# Pico_pinout.net
KiCad netlist of a schematic drawn in Altium Designer
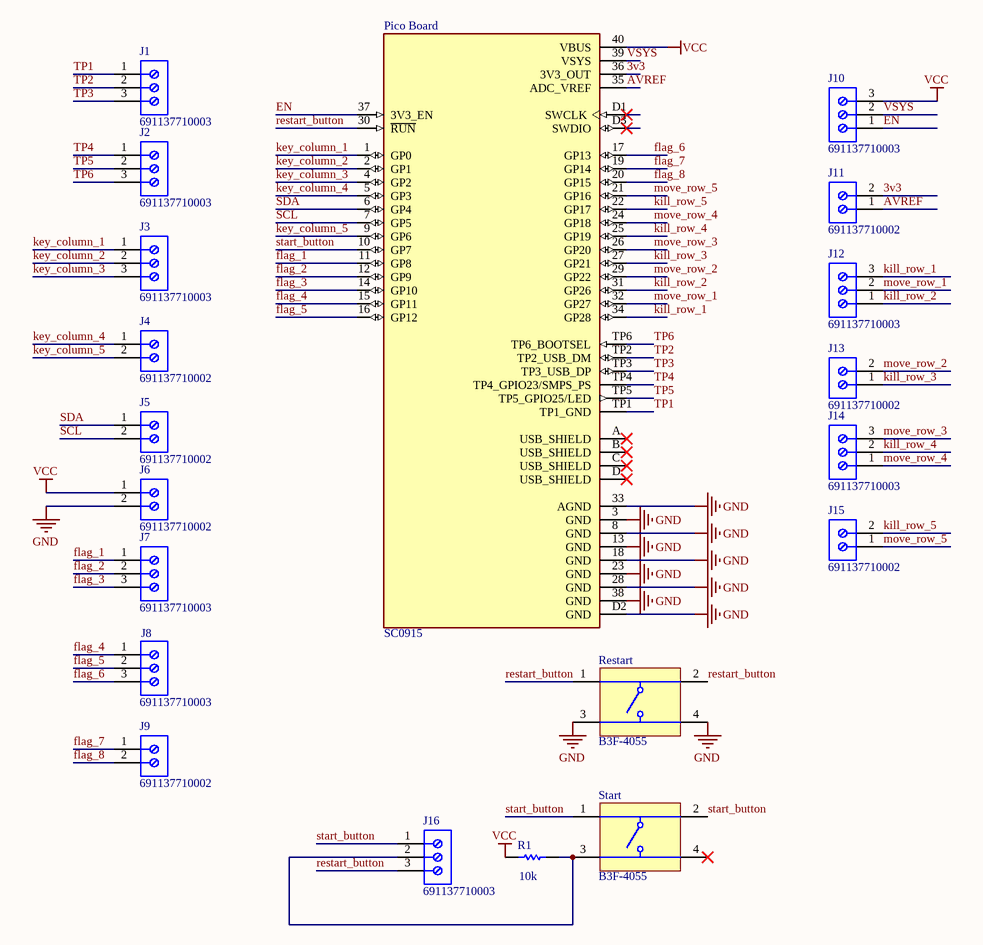
[diagram p0: Pico_pinout.SchDoc]

(export (version "E")
  (design (tool "Eeschema 10.0.6"))
  (components
    (comp (ref "J1")
      (value "691137710003")
      (footprint "691137710003")
      (libsource (lib "Altium Content Vault") (part "TBL - 1R - 03P - Screw"))
    )
    (comp (ref "J2")
      (value "691137710003")
      (footprint "691137710003")
      (libsource (lib "Altium Content Vault") (part "TBL - 1R - 03P - Screw"))
    )
    (comp (ref "J3")
      (value "691137710003")
      (footprint "691137710003")
      (libsource (lib "Altium Content Vault") (part "TBL - 1R - 03P - Screw"))
    )
    (comp (ref "J4")
      (value "691137710002")
      (footprint "691137710002")
      (libsource (lib "Altium Content Vault") (part "TBL - 1R - 02P - Screw"))
    )
    (comp (ref "J5")
      (value "691137710002")
      (footprint "691137710002")
      (libsource (lib "Altium Content Vault") (part "TBL - 1R - 02P - Screw"))
    )
    (comp (ref "J6")
      (value "691137710002")
      (footprint "691137710002")
      (libsource (lib "Altium Content Vault") (part "TBL - 1R - 02P - Screw"))
    )
    (comp (ref "J7")
      (value "691137710003")
      (footprint "691137710003")
      (libsource (lib "Altium Content Vault") (part "TBL - 1R - 03P - Screw"))
    )
    (comp (ref "J8")
      (value "691137710003")
      (footprint "691137710003")
      (libsource (lib "Altium Content Vault") (part "TBL - 1R - 03P - Screw"))
    )
    (comp (ref "J9")
      (value "691137710002")
      (footprint "691137710002")
      (libsource (lib "Altium Content Vault") (part "TBL - 1R - 02P - Screw"))
    )
    (comp (ref "J10")
      (value "691137710003")
      (footprint "691137710003")
      (libsource (lib "Altium Content Vault") (part "TBL - 1R - 03P - Screw"))
    )
    (comp (ref "J11")
      (value "691137710002")
      (footprint "691137710002")
      (libsource (lib "Altium Content Vault") (part "TBL - 1R - 02P - Screw"))
    )
    (comp (ref "J12")
      (value "691137710003")
      (footprint "691137710003")
      (libsource (lib "Altium Content Vault") (part "TBL - 1R - 03P - Screw"))
    )
    (comp (ref "J13")
      (value "691137710002")
      (footprint "691137710002")
      (libsource (lib "Altium Content Vault") (part "TBL - 1R - 02P - Screw"))
    )
    (comp (ref "J14")
      (value "691137710003")
      (footprint "691137710003")
      (libsource (lib "Altium Content Vault") (part "TBL - 1R - 03P - Screw"))
    )
    (comp (ref "J15")
      (value "691137710002")
      (footprint "691137710002")
      (libsource (lib "Altium Content Vault") (part "TBL - 1R - 02P - Screw"))
    )
    (comp (ref "J16")
      (value "691137710003")
      (footprint "691137710003")
      (libsource (lib "Altium Content Vault") (part "TBL - 1R - 03P - Screw"))
    )
    (comp (ref "Pico Board")
      (value "SC0915")
      (footprint "MODULE_SC0915")
      (description "RP2040 Raspberry Pi Pico series ARMÂ® CortexÂ®-M0+ MCU 32-Bit Embedded Evaluation Board")
      (fields (field (name "MF") "Raspberry Pi"))
      (libsource (lib "SC0915 (1)") (part "SC0915"))
    )
    (comp (ref "R1")
      (value "10k")
      (footprint "RESC3116X65X40ML10T20")
      (description "Chip Resistor, 10 KOhm, +/- 1%, 0.25 W, -55 to 155 degC, 1206 (3216 Metric), RoHS, Tape and Reel")
      (fields (field (name "TOLERANCE") "1%") (field (name "MANUFACTURER") "Yageo"))
      (libsource (lib "Altium Content Vault") (part "RES-2"))
    )
    (comp (ref "Restart")
      (value "B3F-4055")
      (footprint "OMRON-B3F-4055_V")
      (description "Tactile Switch, 1 to 50 mA, 100 mOhm Max, 5 to 24 VDC, -25 to 70 degC, 4-Pin THD, RoHS, Bulk")
      (fields (field (name "MANUFACTURER") "OmronElectronics"))
      (libsource (lib "Altium Content Vault") (part "SW-SPST-4_A"))
    )
    (comp (ref "Start")
      (value "B3F-4055")
      (footprint "OMRON-B3F-4055_V")
      (description "Tactile Switch, 1 to 50 mA, 100 mOhm Max, 5 to 24 VDC, -25 to 70 degC, 4-Pin THD, RoHS, Bulk")
      (fields (field (name "MANUFACTURER") "OmronElectronics"))
      (libsource (lib "Altium Content Vault") (part "SW-SPST-4_A"))
    )
  )
  (nets
    (net (code "1") (name "/3v3") (class "Default")
      (node (ref "J11") (pin "2") (pinfunction "2_2") (pintype "passive"))
      (node (ref "Pico Board") (pin "36") (pinfunction "3V3_OUT_36") (pintype "power_in"))
    )
    (net (code "2") (name "/AVREF") (class "Default")
      (node (ref "J11") (pin "1") (pinfunction "1_1") (pintype "passive"))
      (node (ref "Pico Board") (pin "35") (pinfunction "ADC_VREF_35") (pintype "power_in"))
    )
    (net (code "3") (name "/EN") (class "Default")
      (node (ref "J10") (pin "1") (pinfunction "1_1") (pintype "passive"))
      (node (ref "Pico Board") (pin "37") (pinfunction "3V3_EN_37") (pintype "input"))
    )
    (net (code "4") (name "/SCL") (class "Default")
      (node (ref "J5") (pin "2") (pinfunction "2_2") (pintype "passive"))
      (node (ref "Pico Board") (pin "7") (pinfunction "GP5_7") (pintype "bidirectional"))
    )
    (net (code "5") (name "/SDA") (class "Default")
      (node (ref "J5") (pin "1") (pinfunction "1_1") (pintype "passive"))
      (node (ref "Pico Board") (pin "6") (pinfunction "GP4_6") (pintype "bidirectional"))
    )
    (net (code "6") (name "/TP1") (class "Default")
      (node (ref "J1") (pin "1") (pinfunction "1_1") (pintype "passive"))
      (node (ref "Pico Board") (pin "TP1") (pinfunction "TP1_GND_TP1") (pintype "power_in"))
    )
    (net (code "7") (name "/TP2") (class "Default")
      (node (ref "J1") (pin "2") (pinfunction "2_2") (pintype "passive"))
      (node (ref "Pico Board") (pin "TP2") (pinfunction "TP2_USB_DM_TP2") (pintype "bidirectional"))
    )
    (net (code "8") (name "/TP3") (class "Default")
      (node (ref "J1") (pin "3") (pinfunction "3_3") (pintype "passive"))
      (node (ref "Pico Board") (pin "TP3") (pinfunction "TP3_USB_DP_TP3") (pintype "bidirectional"))
    )
    (net (code "9") (name "/TP4") (class "Default")
      (node (ref "J2") (pin "1") (pinfunction "1_1") (pintype "passive"))
      (node (ref "Pico Board") (pin "TP4") (pinfunction "TP4_GPIO23/SMPS_PS_TP4") (pintype "passive"))
    )
    (net (code "10") (name "/TP5") (class "Default")
      (node (ref "J2") (pin "2") (pinfunction "2_2") (pintype "passive"))
      (node (ref "Pico Board") (pin "TP5") (pinfunction "TP5_GPIO25/LED_TP5") (pintype "output"))
    )
    (net (code "11") (name "/TP6") (class "Default")
      (node (ref "J2") (pin "3") (pinfunction "3_3") (pintype "passive"))
      (node (ref "Pico Board") (pin "TP6") (pinfunction "TP6_BOOTSEL_TP6") (pintype "input"))
    )
    (net (code "12") (name "/VSYS") (class "Default")
      (node (ref "J10") (pin "2") (pinfunction "2_2") (pintype "passive"))
      (node (ref "Pico Board") (pin "39") (pinfunction "VSYS_39") (pintype "power_in"))
    )
    (net (code "13") (name "/flag_1") (class "Default")
      (node (ref "J7") (pin "1") (pinfunction "1_1") (pintype "passive"))
      (node (ref "Pico Board") (pin "11") (pinfunction "GP8_11") (pintype "bidirectional"))
    )
    (net (code "14") (name "/flag_2") (class "Default")
      (node (ref "J7") (pin "2") (pinfunction "2_2") (pintype "passive"))
      (node (ref "Pico Board") (pin "12") (pinfunction "GP9_12") (pintype "bidirectional"))
    )
    (net (code "15") (name "/flag_3") (class "Default")
      (node (ref "J7") (pin "3") (pinfunction "3_3") (pintype "passive"))
      (node (ref "Pico Board") (pin "14") (pinfunction "GP10_14") (pintype "bidirectional"))
    )
    (net (code "16") (name "/flag_4") (class "Default")
      (node (ref "J8") (pin "1") (pinfunction "1_1") (pintype "passive"))
      (node (ref "Pico Board") (pin "15") (pinfunction "GP11_15") (pintype "bidirectional"))
    )
    (net (code "17") (name "/flag_5") (class "Default")
      (node (ref "J8") (pin "2") (pinfunction "2_2") (pintype "passive"))
      (node (ref "Pico Board") (pin "16") (pinfunction "GP12_16") (pintype "bidirectional"))
    )
    (net (code "18") (name "/flag_6") (class "Default")
      (node (ref "J8") (pin "3") (pinfunction "3_3") (pintype "passive"))
      (node (ref "Pico Board") (pin "17") (pinfunction "GP13_17") (pintype "bidirectional"))
    )
    (net (code "19") (name "/flag_7") (class "Default")
      (node (ref "J9") (pin "1") (pinfunction "1_1") (pintype "passive"))
      (node (ref "Pico Board") (pin "19") (pinfunction "GP14_19") (pintype "bidirectional"))
    )
    (net (code "20") (name "/flag_8") (class "Default")
      (node (ref "J9") (pin "2") (pinfunction "2_2") (pintype "passive"))
      (node (ref "Pico Board") (pin "20") (pinfunction "GP15_20") (pintype "bidirectional"))
    )
    (net (code "21") (name "/key_column_1") (class "Default")
      (node (ref "J3") (pin "1") (pinfunction "1_1") (pintype "passive"))
      (node (ref "Pico Board") (pin "1") (pinfunction "GP0_1") (pintype "bidirectional"))
    )
    (net (code "22") (name "/key_column_2") (class "Default")
      (node (ref "J3") (pin "2") (pinfunction "2_2") (pintype "passive"))
      (node (ref "Pico Board") (pin "2") (pinfunction "GP1_2") (pintype "bidirectional"))
    )
    (net (code "23") (name "/key_column_3") (class "Default")
      (node (ref "J3") (pin "3") (pinfunction "3_3") (pintype "passive"))
      (node (ref "Pico Board") (pin "4") (pinfunction "GP2_4") (pintype "bidirectional"))
    )
    (net (code "24") (name "/key_column_4") (class "Default")
      (node (ref "J4") (pin "1") (pinfunction "1_1") (pintype "passive"))
      (node (ref "Pico Board") (pin "5") (pinfunction "GP3_5") (pintype "bidirectional"))
    )
    (net (code "25") (name "/key_column_5") (class "Default")
      (node (ref "J4") (pin "2") (pinfunction "2_2") (pintype "passive"))
      (node (ref "Pico Board") (pin "9") (pinfunction "GP6_9") (pintype "bidirectional"))
    )
    (net (code "26") (name "/kill_row_1") (class "Default")
      (node (ref "J12") (pin "3") (pinfunction "3_3") (pintype "passive"))
      (node (ref "Pico Board") (pin "34") (pinfunction "GP28_34") (pintype "bidirectional"))
    )
    (net (code "27") (name "/kill_row_2") (class "Default")
      (node (ref "J12") (pin "1") (pinfunction "1_1") (pintype "passive"))
      (node (ref "Pico Board") (pin "31") (pinfunction "GP26_31") (pintype "bidirectional"))
    )
    (net (code "28") (name "/kill_row_3") (class "Default")
      (node (ref "J13") (pin "1") (pinfunction "1_1") (pintype "passive"))
      (node (ref "Pico Board") (pin "27") (pinfunction "GP21_27") (pintype "bidirectional"))
    )
    (net (code "29") (name "/kill_row_4") (class "Default")
      (node (ref "J14") (pin "2") (pinfunction "2_2") (pintype "passive"))
      (node (ref "Pico Board") (pin "25") (pinfunction "GP19_25") (pintype "bidirectional"))
    )
    (net (code "30") (name "/kill_row_5") (class "Default")
      (node (ref "J15") (pin "2") (pinfunction "2_2") (pintype "passive"))
      (node (ref "Pico Board") (pin "22") (pinfunction "GP17_22") (pintype "bidirectional"))
    )
    (net (code "31") (name "/move_row_1") (class "Default")
      (node (ref "J12") (pin "2") (pinfunction "2_2") (pintype "passive"))
      (node (ref "Pico Board") (pin "32") (pinfunction "GP27_32") (pintype "bidirectional"))
    )
    (net (code "32") (name "/move_row_2") (class "Default")
      (node (ref "J13") (pin "2") (pinfunction "2_2") (pintype "passive"))
      (node (ref "Pico Board") (pin "29") (pinfunction "GP22_29") (pintype "bidirectional"))
    )
    (net (code "33") (name "/move_row_3") (class "Default")
      (node (ref "J14") (pin "3") (pinfunction "3_3") (pintype "passive"))
      (node (ref "Pico Board") (pin "26") (pinfunction "GP20_26") (pintype "bidirectional"))
    )
    (net (code "34") (name "/move_row_4") (class "Default")
      (node (ref "J14") (pin "1") (pinfunction "1_1") (pintype "passive"))
      (node (ref "Pico Board") (pin "24") (pinfunction "GP18_24") (pintype "bidirectional"))
    )
    (net (code "35") (name "/move_row_5") (class "Default")
      (node (ref "J15") (pin "1") (pinfunction "1_1") (pintype "passive"))
      (node (ref "Pico Board") (pin "21") (pinfunction "GP16_21") (pintype "bidirectional"))
    )
    (net (code "36") (name "/restart_button") (class "Default")
      (node (ref "J16") (pin "3") (pinfunction "3_3") (pintype "passive"))
      (node (ref "Pico Board") (pin "30") (pinfunction "~{RUN}_30") (pintype "input"))
      (node (ref "Restart") (pin "1") (pinfunction "1_1") (pintype "passive"))
      (node (ref "Restart") (pin "2") (pinfunction "2_2") (pintype "passive"))
    )
    (net (code "37") (name "/start_button") (class "Default")
      (node (ref "J16") (pin "1") (pinfunction "1_1") (pintype "passive"))
      (node (ref "Pico Board") (pin "10") (pinfunction "GP7_10") (pintype "bidirectional"))
      (node (ref "Start") (pin "1") (pinfunction "1_1") (pintype "passive"))
      (node (ref "Start") (pin "2") (pinfunction "2_2") (pintype "passive"))
    )
    (net (code "38") (name "GND") (class "Default")
      (node (ref "J6") (pin "2") (pinfunction "2_2") (pintype "passive"))
      (node (ref "Pico Board") (pin "13") (pinfunction "GND_13") (pintype "power_in"))
      (node (ref "Pico Board") (pin "18") (pinfunction "GND_18") (pintype "power_in"))
      (node (ref "Pico Board") (pin "23") (pinfunction "GND_23") (pintype "power_in"))
      (node (ref "Pico Board") (pin "28") (pinfunction "GND_28") (pintype "power_in"))
      (node (ref "Pico Board") (pin "3") (pinfunction "GND_3") (pintype "power_in"))
      (node (ref "Pico Board") (pin "33") (pinfunction "AGND_33") (pintype "power_in"))
      (node (ref "Pico Board") (pin "38") (pinfunction "GND_38") (pintype "power_in"))
      (node (ref "Pico Board") (pin "8") (pinfunction "GND_8") (pintype "power_in"))
      (node (ref "Pico Board") (pin "D2") (pinfunction "GND_D2") (pintype "power_in"))
      (node (ref "Restart") (pin "3") (pinfunction "3_3") (pintype "passive"))
      (node (ref "Restart") (pin "4") (pinfunction "4_4") (pintype "passive"))
    )
    (net (code "39") (name "Net-(J16-Pad2)") (class "Default")
      (node (ref "J16") (pin "2") (pinfunction "2_2") (pintype "passive"))
      (node (ref "R1") (pin "2") (pinfunction "2_2") (pintype "passive"))
      (node (ref "Start") (pin "3") (pinfunction "3_3") (pintype "passive"))
    )
    (net (code "40") (name "VCC") (class "Default")
      (node (ref "J10") (pin "3") (pinfunction "3_3") (pintype "passive"))
      (node (ref "J6") (pin "1") (pinfunction "1_1") (pintype "passive"))
      (node (ref "Pico Board") (pin "40") (pinfunction "VBUS_40") (pintype "power_in"))
      (node (ref "R1") (pin "1") (pinfunction "1_1") (pintype "passive"))
    )
    (net (code "41") (name "unconnected-(Pico Board-SWCLK-PadD1)") (class "Default")
      (node (ref "Pico Board") (pin "D1") (pinfunction "SWCLK_D1") (pintype "input+no_connect"))
    )
    (net (code "42") (name "unconnected-(Pico Board-SWDIO-PadD3)") (class "Default")
      (node (ref "Pico Board") (pin "D3") (pinfunction "SWDIO_D3") (pintype "bidirectional+no_connect"))
    )
    (net (code "43") (name "unconnected-(Pico Board-USB_SHIELD-PadA)") (class "Default")
      (node (ref "Pico Board") (pin "A") (pinfunction "USB_SHIELD_A") (pintype "power_in+no_connect"))
    )
    (net (code "44") (name "unconnected-(Pico Board-USB_SHIELD-PadB)") (class "Default")
      (node (ref "Pico Board") (pin "B") (pinfunction "USB_SHIELD_B") (pintype "power_in+no_connect"))
    )
    (net (code "45") (name "unconnected-(Pico Board-USB_SHIELD-PadC)") (class "Default")
      (node (ref "Pico Board") (pin "C") (pinfunction "USB_SHIELD_C") (pintype "power_in+no_connect"))
    )
    (net (code "46") (name "unconnected-(Pico Board-USB_SHIELD-PadD)") (class "Default")
      (node (ref "Pico Board") (pin "D") (pinfunction "USB_SHIELD_D") (pintype "power_in+no_connect"))
    )
    (net (code "47") (name "unconnected-(Start-Pad4)") (class "Default")
      (node (ref "Start") (pin "4") (pinfunction "4_4") (pintype "passive+no_connect"))
    )
  )
)
